# PX4FLOW2_0_Power_X0.net
KiCad netlist of a schematic drawn in Altium Designer
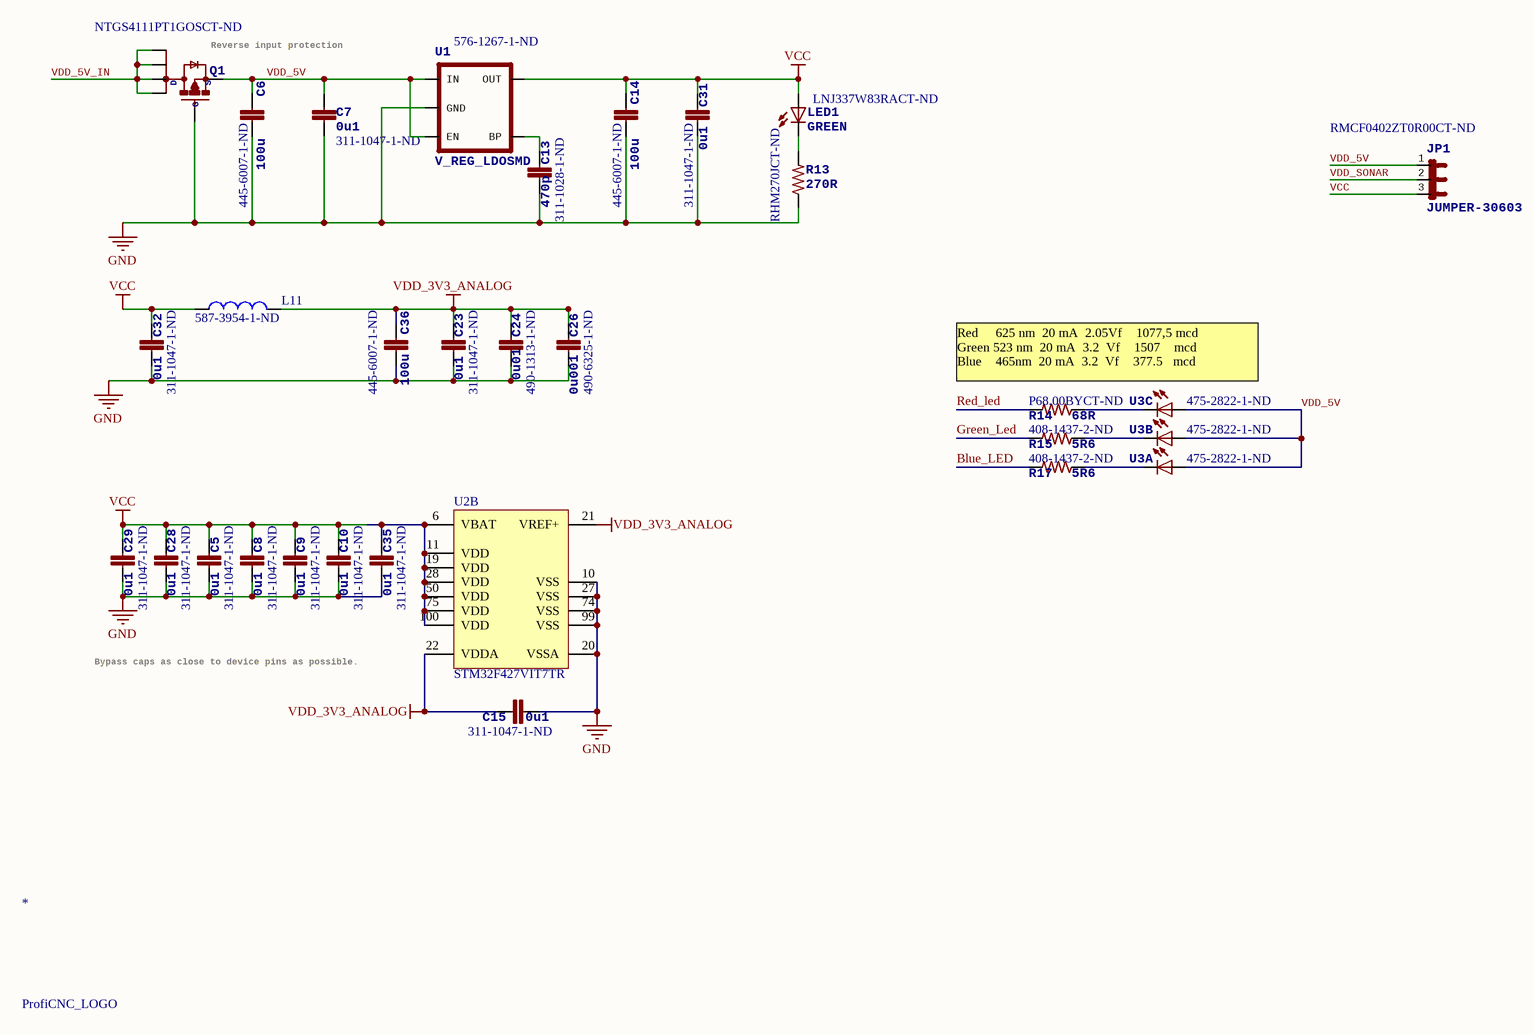
[diagram p0: PX4FLOW2.0_Power_X0.SchDoc]

(export (version "E")
  (design (tool "Eeschema 10.0.6"))
  (components
    (comp (ref "C5")
      (value "0u1")
      (footprint "0402-CAP")
      (description "CapacitorStandard 0603 ceramic capacitor, and 0.1\" leaded capacitor.")
      (fields
        (field (name "PARTNO") "CC0402ZRY5V7BB104")
        (field (name "SUPPLIER PART NUMBER 1") "311-1047-1-ND")
      )
      (libsource (lib "pixhawk2") (part "CAP0402-CAP"))
    )
    (comp (ref "C6")
      (value "100u")
      (footprint "1206-CAP")
      (description "CAP CER 100UF 10V 20% X5R 1206")
      (fields
        (field (name "PARTNO") "C3216X5R1A107M160AC")
        (field (name "SUPPLIER PART NUMBER 1") "445-6007-1-ND")
        (field (name "3DR_PARTNO") "ECM0716")
      )
      (libsource (lib "pixhawk2") (part "CAP1206"))
    )
    (comp (ref "C7")
      (value "0u1")
      (footprint "0402-CAP")
      (description "CapacitorStandard 0603 ceramic capacitor, and 0.1\" leaded capacitor.")
      (fields
        (field (name "PARTNO") "CC0402ZRY5V7BB104")
        (field (name "SUPPLIER PART NUMBER 1") "311-1047-1-ND")
      )
      (libsource (lib "") (part "CAP0402-CAP_2"))
    )
    (comp (ref "C8")
      (value "0u1")
      (footprint "0402-CAP")
      (description "CapacitorStandard 0603 ceramic capacitor, and 0.1\" leaded capacitor.")
      (fields
        (field (name "PARTNO") "CC0402ZRY5V7BB104")
        (field (name "SUPPLIER PART NUMBER 1") "311-1047-1-ND")
      )
      (libsource (lib "pixhawk2") (part "CAP0402-CAP"))
    )
    (comp (ref "C9")
      (value "0u1")
      (footprint "0402-CAP")
      (description "CapacitorStandard 0603 ceramic capacitor, and 0.1\" leaded capacitor.")
      (fields
        (field (name "PARTNO") "CC0402ZRY5V7BB104")
        (field (name "SUPPLIER PART NUMBER 1") "311-1047-1-ND")
      )
      (libsource (lib "pixhawk2") (part "CAP0402-CAP"))
    )
    (comp (ref "C10")
      (value "0u1")
      (footprint "0402-CAP")
      (description "CapacitorStandard 0603 ceramic capacitor, and 0.1\" leaded capacitor.")
      (fields
        (field (name "PARTNO") "CC0402ZRY5V7BB104")
        (field (name "SUPPLIER PART NUMBER 1") "311-1047-1-ND")
      )
      (libsource (lib "pixhawk2") (part "CAP0402-CAP"))
    )
    (comp (ref "C13")
      (value "470p")
      (footprint "0402-CAP")
      (description "CapacitorStandard 0603 ceramic capacitor, and 0.1\" leaded capacitor.")
      (fields
        (field (name "PARTNO") "CC0402KRX7R9BB471")
        (field (name "SUPPLIER PART NUMBER 1") "311-1028-1-ND")
      )
      (libsource (lib "pixhawk2") (part "CAP0402-CAP"))
    )
    (comp (ref "C14")
      (value "100u")
      (footprint "1206-CAP")
      (description "CAP CER 100UF 10V 20% X5R 1206")
      (fields
        (field (name "PARTNO") "C3216X5R1A107M160AC")
        (field (name "SUPPLIER PART NUMBER 1") "445-6007-1-ND")
        (field (name "3DR_PARTNO") "ECM0716")
      )
      (libsource (lib "pixhawk2") (part "CAP1206"))
    )
    (comp (ref "C15")
      (value "0u1")
      (footprint "0402-CAP")
      (description "CapacitorStandard 0603 ceramic capacitor, and 0.1\" leaded capacitor.")
      (fields
        (field (name "PARTNO") "CC0402ZRY5V7BB104")
        (field (name "SUPPLIER PART NUMBER 1") "311-1047-1-ND")
      )
      (libsource (lib "") (part "CAP0402-CAP_1"))
    )
    (comp (ref "C23")
      (value "0u1")
      (footprint "0402-CAP")
      (description "CapacitorStandard 0603 ceramic capacitor, and 0.1\" leaded capacitor.")
      (fields
        (field (name "PARTNO") "CC0402ZRY5V7BB104")
        (field (name "SUPPLIER PART NUMBER 1") "311-1047-1-ND")
      )
      (libsource (lib "pixhawk2") (part "CAP0402-CAP"))
    )
    (comp (ref "C24")
      (value "0u01")
      (footprint "0402-CAP")
      (description "CapacitorStandard 0603 ceramic capacitor, and 0.1\" leaded capacitor.")
      (fields
        (field (name "PARTNO") "CC0402ZRY5V7BB104")
        (field (name "SUPPLIER PART NUMBER 1") "490-1313-1-ND")
      )
      (libsource (lib "pixhawk2") (part "CAP0402-CAP"))
    )
    (comp (ref "C26")
      (value "0u001")
      (footprint "0402-CAP")
      (description "CapacitorStandard 0603 ceramic capacitor, and 0.1\" leaded capacitor.")
      (fields
        (field (name "PARTNO") "CC0402ZRY5V7BB104")
        (field (name "SUPPLIER PART NUMBER 1") "490-6325-1-ND")
      )
      (libsource (lib "pixhawk2") (part "CAP0402-CAP"))
    )
    (comp (ref "C28")
      (value "0u1")
      (footprint "0402-CAP")
      (description "CapacitorStandard 0603 ceramic capacitor, and 0.1\" leaded capacitor.")
      (fields
        (field (name "PARTNO") "CC0402ZRY5V7BB104")
        (field (name "SUPPLIER PART NUMBER 1") "311-1047-1-ND")
      )
      (libsource (lib "pixhawk2") (part "CAP0402-CAP"))
    )
    (comp (ref "C29")
      (value "0u1")
      (footprint "0402-CAP")
      (description "CapacitorStandard 0603 ceramic capacitor, and 0.1\" leaded capacitor.")
      (fields
        (field (name "PARTNO") "CC0402ZRY5V7BB104")
        (field (name "SUPPLIER PART NUMBER 1") "311-1047-1-ND")
      )
      (libsource (lib "pixhawk2") (part "CAP0402-CAP"))
    )
    (comp (ref "C31")
      (value "0u1")
      (footprint "0402-CAP")
      (description "CapacitorStandard 0603 ceramic capacitor, and 0.1\" leaded capacitor.")
      (fields
        (field (name "PARTNO") "CC0402ZRY5V7BB104")
        (field (name "SUPPLIER PART NUMBER 1") "311-1047-1-ND")
      )
      (libsource (lib "pixhawk2") (part "CAP0402-CAP"))
    )
    (comp (ref "C32")
      (value "0u1")
      (footprint "0402-CAP")
      (description "CapacitorStandard 0603 ceramic capacitor, and 0.1\" leaded capacitor.")
      (fields
        (field (name "PARTNO") "CC0402ZRY5V7BB104")
        (field (name "SUPPLIER PART NUMBER 1") "311-1047-1-ND")
      )
      (libsource (lib "pixhawk2") (part "CAP0402-CAP"))
    )
    (comp (ref "C35")
      (value "0u1")
      (footprint "0402-CAP")
      (description "0402")
      (fields
        (field (name "PARTNO") "CC0402ZRY5V7BB104")
        (field (name "SUPPLIER PART NUMBER 1") "311-1047-1-ND")
      )
      (libsource (lib "pixhawk2") (part "CAP0402-CAP"))
    )
    (comp (ref "C36")
      (value "100u")
      (footprint "1206-CAP")
      (description "CAP CER 100UF 10V 20% X5R 1206")
      (fields
        (field (name "PARTNO") "C3216X5R1A107M160AC")
        (field (name "SUPPLIER PART NUMBER 1") "445-6007-1-ND")
        (field (name "3DR_PARTNO") "ECM0716")
      )
      (libsource (lib "pixhawk2") (part "CAP1206"))
    )
    (comp (ref "JP1")
      (value "JUMPER-30603")
      (footprint "SJ_3_0603_PASTE1&2")
      (fields
        (field (name "PARTNO") "RMCF0402ZT0R00")
        (field (name "SUPPLIER PART NUMBER 1") "RMCF0402ZT0R00CT-ND")
      )
      (libsource (lib "pixhawk2") (part "JUMPER-30603"))
    )
    (comp (ref "L11")
      (value "Inductor")
      (footprint "L0402")
      (description "FERRITE BEAD 120 OHM 0402")
      (fields (field (name "SUPPLIER PART NUMBER 1") "587-3954-1-ND"))
      (libsource (lib "3DR") (part "Inductor"))
    )
    (comp (ref "LED1")
      (value "GREEN")
      (footprint "LED-0603")
      (description "Green LED")
      (fields
        (field (name "PARTNO") "LNJ337W83RA")
        (field (name "SUPPLIER PART NUMBER 1") "LNJ337W83RACT-ND")
      )
      (libsource (lib "pixhawk2") (part "LED0603"))
    )
    (comp (ref "Q1")
      (value "NTGS4111P")
      (footprint "TSOP-6")
      (fields
        (field (name "D") "D")
        (field (name "S") "S")
        (field (name "G") "G")
        (field (name "SUPPLIER PART NUMBER 1") "NTGS4111PT1GOSCT-ND")
      )
      (libsource (lib "pixhawk2") (part "NTGS4111P"))
    )
    (comp (ref "R13")
      (value "270R")
      (footprint "R0402")
      (fields (field (name "PARTNO") "MCR01MZPJ271") (field (name "SUPPLIER PART NUMBER 1") "RHM270JCT-ND"))
      (libsource (lib "pixhawk2") (part "RESISTOR0402-RES"))
    )
    (comp (ref "R14")
      (value "68R")
      (footprint "0603-RES")
      (description "RES SMD 68 OHM 1% 1/4W 0603")
      (fields (field (name "PARTNO") "ERJ-PA3F68R0V") (field (name "SUPPLIER PART NUMBER 1") "P68.00BYCT-ND"))
      (libsource (lib "pixhawk2") (part "RESISTOR0402-RES"))
    )
    (comp (ref "R15")
      (value "5R6")
      (footprint "0603-RES")
      (description "RES SMD 5.6 OHM 1% 1/5W 0603")
      (fields (field (name "PARTNO") "RL0816S-5R6-F") (field (name "SUPPLIER PART NUMBER 1") "408-1437-2-ND"))
      (libsource (lib "pixhawk2") (part "RESISTOR0402-RES"))
    )
    (comp (ref "R17")
      (value "5R6")
      (footprint "0603-RES")
      (description "RES SMD 5.6 OHM 1% 1/5W 0603")
      (fields (field (name "PARTNO") "RL0816S-5R6-F") (field (name "SUPPLIER PART NUMBER 1") "408-1437-2-ND"))
      (libsource (lib "pixhawk2") (part "RESISTOR0402-RES"))
    )
    (comp (ref "U1")
      (value "V_REG_LDOSMD")
      (footprint "SOT23-5")
      (fields
        (field (name "PARTNO") "MIC5207-3.3YM5")
        (field (name "SUPPLIER PART NUMBER 1") "576-1267-1-ND")
      )
      (libsource (lib "pixhawk2") (part "V_REG_LDOSMD"))
    )
    (comp (ref "U2")
      (value "STM32F427VIT7TR")
      (footprint "STM-LQFP100_N")
      (fields (field (name "MANUFACTURER") "STMicroelectronics"))
      (libsource (lib "STMicroelectronics STM32 F4") (part "STM32F427VIT7TR"))
    )
    (comp (ref "U3")
      (value "LRTB GFTG-T7AW-1+V7A7-29+R5T9-49-L")
      (footprint "6-PLCC")
      (description "RGB LED with separate anode/cathode terminals")
      (fields (field (name "SUPPLIER PART NUMBER 1") "475-2822-1-ND"))
      (libsource (lib "pixhawk2") (part "RGB-LED6-PLCC"))
    )
  )
  (nets
    (net (code "1") (name "/Blue_LED") (class "Default")
      (node (ref "R17") (pin "2") (pinfunction "2_2") (pintype "passive"))
    )
    (net (code "2") (name "/Green_Led") (class "Default")
      (node (ref "R15") (pin "2") (pinfunction "2_2") (pintype "passive"))
    )
    (net (code "3") (name "/Red_led") (class "Default")
      (node (ref "R14") (pin "2") (pinfunction "2_2") (pintype "passive"))
    )
    (net (code "4") (name "/VDD_5V") (class "Default")
      (node (ref "C6") (pin "P$1") (pinfunction "1_P$1") (pintype "passive"))
      (node (ref "C7") (pin "2") (pinfunction "2_2") (pintype "passive"))
      (node (ref "JP1") (pin "1") (pinfunction "1_1") (pintype "passive"))
      (node (ref "Q1") (pin "4") (pinfunction "S_4") (pintype "passive"))
      (node (ref "U1") (pin "1") (pinfunction "IN_1") (pintype "passive"))
      (node (ref "U1") (pin "3") (pinfunction "EN_3") (pintype "passive"))
      (node (ref "U3") (pin "A1") (pinfunction "A_A1") (pintype "passive"))
      (node (ref "U3") (pin "A2") (pinfunction "A_A2") (pintype "passive"))
      (node (ref "U3") (pin "A3") (pinfunction "A_A3") (pintype "passive"))
    )
    (net (code "5") (name "/VDD_5V_IN") (class "Default")
      (node (ref "Q1") (pin "1") (pinfunction "D_1") (pintype "passive"))
      (node (ref "Q1") (pin "2") (pinfunction "D1_2") (pintype "passive"))
      (node (ref "Q1") (pin "5") (pinfunction "D2_5") (pintype "passive"))
      (node (ref "Q1") (pin "6") (pinfunction "D3_6") (pintype "passive"))
    )
    (net (code "6") (name "/VDD_SONAR") (class "Default")
      (node (ref "JP1") (pin "2") (pinfunction "2_2") (pintype "passive"))
    )
    (net (code "7") (name "GND") (class "Default")
      (node (ref "C10") (pin "2") (pinfunction "2_2") (pintype "passive"))
      (node (ref "C13") (pin "2") (pinfunction "2_2") (pintype "passive"))
      (node (ref "C14") (pin "P$2") (pinfunction "2_P$2") (pintype "passive"))
      (node (ref "C15") (pin "2") (pinfunction "2_2") (pintype "passive"))
      (node (ref "C23") (pin "2") (pinfunction "2_2") (pintype "passive"))
      (node (ref "C24") (pin "2") (pinfunction "2_2") (pintype "passive"))
      (node (ref "C26") (pin "2") (pinfunction "2_2") (pintype "passive"))
      (node (ref "C28") (pin "2") (pinfunction "2_2") (pintype "passive"))
      (node (ref "C29") (pin "2") (pinfunction "2_2") (pintype "passive"))
      (node (ref "C31") (pin "2") (pinfunction "2_2") (pintype "passive"))
      (node (ref "C32") (pin "2") (pinfunction "2_2") (pintype "passive"))
      (node (ref "C35") (pin "2") (pinfunction "2_2") (pintype "passive"))
      (node (ref "C36") (pin "P$2") (pinfunction "2_P$2") (pintype "passive"))
      (node (ref "C5") (pin "2") (pinfunction "2_2") (pintype "passive"))
      (node (ref "C6") (pin "P$2") (pinfunction "2_P$2") (pintype "passive"))
      (node (ref "C7") (pin "1") (pinfunction "1_1") (pintype "passive"))
      (node (ref "C8") (pin "2") (pinfunction "2_2") (pintype "passive"))
      (node (ref "C9") (pin "2") (pinfunction "2_2") (pintype "passive"))
      (node (ref "Q1") (pin "3") (pinfunction "G_3") (pintype "passive"))
      (node (ref "R13") (pin "1") (pinfunction "1_1") (pintype "passive"))
      (node (ref "U1") (pin "2") (pinfunction "GND_2") (pintype "power_in"))
      (node (ref "U2") (pin "10") (pinfunction "VSS_10") (pintype "power_in"))
      (node (ref "U2") (pin "20") (pinfunction "VSSA_20") (pintype "power_in"))
      (node (ref "U2") (pin "27") (pinfunction "VSS_27") (pintype "power_in"))
      (node (ref "U2") (pin "74") (pinfunction "VSS_74") (pintype "power_in"))
      (node (ref "U2") (pin "99") (pinfunction "VSS_99") (pintype "power_in"))
    )
    (net (code "8") (name "Net-(LED1-PadC)") (class "Default")
      (node (ref "LED1") (pin "C") (pinfunction "C_C") (pintype "passive"))
      (node (ref "R13") (pin "2") (pinfunction "2_2") (pintype "passive"))
    )
    (net (code "9") (name "Net-(U1-BP)") (class "Default")
      (node (ref "C13") (pin "1") (pinfunction "1_1") (pintype "passive"))
      (node (ref "U1") (pin "4") (pinfunction "BP_4") (pintype "passive"))
    )
    (net (code "10") (name "Net-(U3A-C)") (class "Default")
      (node (ref "R17") (pin "1") (pinfunction "1_1") (pintype "passive"))
      (node (ref "U3") (pin "C1") (pinfunction "C_C1") (pintype "passive"))
    )
    (net (code "11") (name "Net-(U3B-C)") (class "Default")
      (node (ref "R15") (pin "1") (pinfunction "1_1") (pintype "passive"))
      (node (ref "U3") (pin "C2") (pinfunction "C_C2") (pintype "passive"))
    )
    (net (code "12") (name "Net-(U3C-C)") (class "Default")
      (node (ref "R14") (pin "1") (pinfunction "1_1") (pintype "passive"))
      (node (ref "U3") (pin "C3") (pinfunction "C_C3") (pintype "passive"))
    )
    (net (code "13") (name "VCC") (class "Default")
      (node (ref "C10") (pin "1") (pinfunction "1_1") (pintype "passive"))
      (node (ref "C14") (pin "P$1") (pinfunction "1_P$1") (pintype "passive"))
      (node (ref "C28") (pin "1") (pinfunction "1_1") (pintype "passive"))
      (node (ref "C29") (pin "1") (pinfunction "1_1") (pintype "passive"))
      (node (ref "C31") (pin "1") (pinfunction "1_1") (pintype "passive"))
      (node (ref "C32") (pin "1") (pinfunction "1_1") (pintype "passive"))
      (node (ref "C35") (pin "1") (pinfunction "1_1") (pintype "passive"))
      (node (ref "C5") (pin "1") (pinfunction "1_1") (pintype "passive"))
      (node (ref "C8") (pin "1") (pinfunction "1_1") (pintype "passive"))
      (node (ref "C9") (pin "1") (pinfunction "1_1") (pintype "passive"))
      (node (ref "JP1") (pin "3") (pinfunction "3_3") (pintype "passive"))
      (node (ref "L11") (pin "1") (pinfunction "1_1") (pintype "passive"))
      (node (ref "LED1") (pin "A") (pinfunction "A_A") (pintype "passive"))
      (node (ref "U1") (pin "5") (pinfunction "OUT_5") (pintype "passive"))
      (node (ref "U2") (pin "100") (pinfunction "VDD_100") (pintype "power_in"))
      (node (ref "U2") (pin "11") (pinfunction "VDD_11") (pintype "power_in"))
      (node (ref "U2") (pin "19") (pinfunction "VDD_19") (pintype "power_in"))
      (node (ref "U2") (pin "28") (pinfunction "VDD_28") (pintype "power_in"))
      (node (ref "U2") (pin "50") (pinfunction "VDD_50") (pintype "power_in"))
      (node (ref "U2") (pin "6") (pinfunction "VBAT_6") (pintype "power_in"))
      (node (ref "U2") (pin "75") (pinfunction "VDD_75") (pintype "power_in"))
    )
    (net (code "14") (name "VDD_3V3_ANALOG") (class "Default")
      (node (ref "C15") (pin "1") (pinfunction "1_1") (pintype "passive"))
      (node (ref "C23") (pin "1") (pinfunction "1_1") (pintype "passive"))
      (node (ref "C24") (pin "1") (pinfunction "1_1") (pintype "passive"))
      (node (ref "C26") (pin "1") (pinfunction "1_1") (pintype "passive"))
      (node (ref "C36") (pin "P$1") (pinfunction "1_P$1") (pintype "passive"))
      (node (ref "L11") (pin "2") (pinfunction "2_2") (pintype "passive"))
      (node (ref "U2") (pin "21") (pinfunction "VREF+_21") (pintype "power_in"))
      (node (ref "U2") (pin "22") (pinfunction "VDDA_22") (pintype "power_in"))
    )
  )
)
